# icyradio-lna.net
KiCad netlist of a schematic drawn in EAGLE
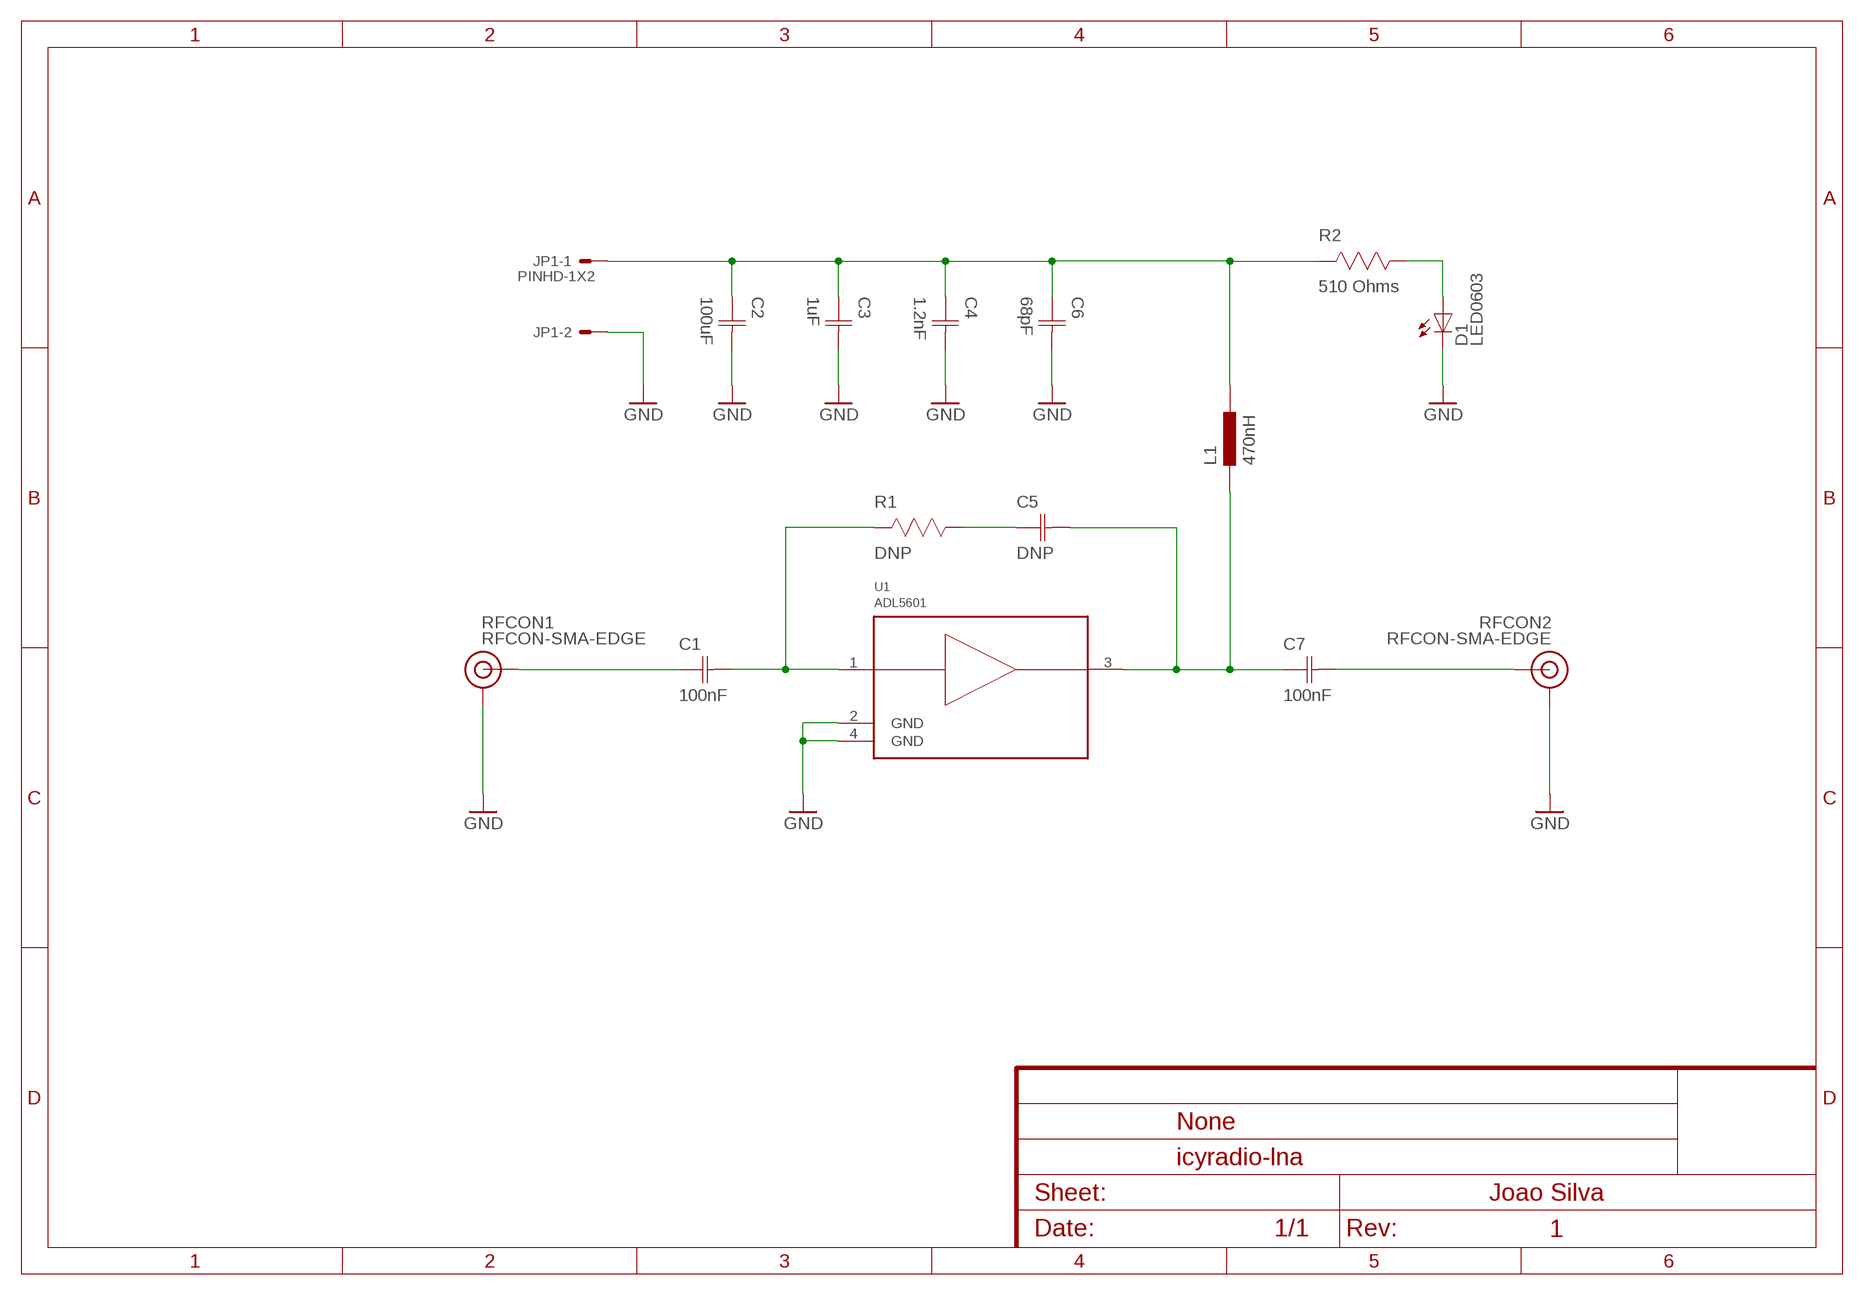
[diagram p0: schematic, sheet 1]

(export (version "E")
  (design (tool "Eeschema 10.0.6"))
  (components
    (comp (ref "C1")
      (value "100nF")
      (footprint "eagle-import:CAP0603")
      (libsource (lib "eagle-import") (part "CAPACITOR-0603"))
    )
    (comp (ref "C2")
      (value "100uF")
      (footprint "eagle-import:CAP1206")
      (libsource (lib "eagle-import") (part "CAPACITOR-1206"))
    )
    (comp (ref "C3")
      (value "1uF")
      (footprint "eagle-import:CAP0603")
      (libsource (lib "eagle-import") (part "CAPACITOR-0603"))
    )
    (comp (ref "C4")
      (value "1.2nF")
      (footprint "eagle-import:CAP0603")
      (libsource (lib "eagle-import") (part "CAPACITOR-0603"))
    )
    (comp (ref "C5")
      (value "DNP")
      (footprint "eagle-import:CAP0603")
      (libsource (lib "eagle-import") (part "CAPACITOR-0603"))
    )
    (comp (ref "C6")
      (value "68pF")
      (footprint "eagle-import:CAP0603")
      (libsource (lib "eagle-import") (part "CAPACITOR-0603"))
    )
    (comp (ref "C7")
      (value "100nF")
      (footprint "eagle-import:CAP0603")
      (libsource (lib "eagle-import") (part "CAPACITOR-0603"))
    )
    (comp (ref "D1")
      (value "LED0603")
      (footprint "eagle-import:0603")
      (libsource (lib "eagle-import") (part "LED0603"))
    )
    (comp (ref "JP1")
      (value "PINHD-1X2")
      (footprint "eagle-import:1X02")
      (libsource (lib "eagle-import") (part "PINHD-1X2"))
    )
    (comp (ref "L1")
      (value "470nH")
      (footprint "eagle-import:IND0603")
      (libsource (lib "eagle-import") (part "INDUCTOR-0603"))
    )
    (comp (ref "R1")
      (value "DNP")
      (footprint "eagle-import:RES0603")
      (libsource (lib "eagle-import") (part "RESISTOR-0603"))
    )
    (comp (ref "R2")
      (value "510 Ohms")
      (footprint "eagle-import:RES0603")
      (libsource (lib "eagle-import") (part "RESISTOR-0603"))
    )
    (comp (ref "RFCON1")
      (value "RFCON-SMA-EDGE")
      (footprint "eagle-import:SMA-EDGE")
      (libsource (lib "eagle-import") (part "RFCON-SMA-EDGE"))
    )
    (comp (ref "RFCON2")
      (value "RFCON-SMA-EDGE")
      (footprint "eagle-import:SMA-EDGE")
      (libsource (lib "eagle-import") (part "RFCON-SMA-EDGE"))
    )
    (comp (ref "U1")
      (value "ADL5601")
      (footprint "eagle-import:SOT89")
      (libsource (lib "eagle-import") (part "ADL5?601"))
    )
  )
  (nets
    (net (code "1") (name "GND") (class "Default")
      (node (ref "C2") (pin "2") (pinfunction "C2_2") (pintype "passive"))
      (node (ref "C3") (pin "2") (pinfunction "C2_2") (pintype "passive"))
      (node (ref "C4") (pin "2") (pinfunction "C2_2") (pintype "passive"))
      (node (ref "C6") (pin "2") (pinfunction "C2_2") (pintype "passive"))
      (node (ref "D1") (pin "C") (pinfunction "C_C") (pintype "passive"))
      (node (ref "JP1") (pin "2") (pinfunction "S_2") (pintype "passive"))
      (node (ref "RFCON1") (pin "GND@0") (pinfunction "GND_GND@0") (pintype "bidirectional"))
      (node (ref "RFCON1") (pin "GND@1") (pinfunction "GND_GND@1") (pintype "bidirectional"))
      (node (ref "RFCON1") (pin "GND@2") (pinfunction "GND_GND@2") (pintype "bidirectional"))
      (node (ref "RFCON1") (pin "GND@3") (pinfunction "GND_GND@3") (pintype "bidirectional"))
      (node (ref "RFCON2") (pin "GND@0") (pinfunction "GND_GND@0") (pintype "bidirectional"))
      (node (ref "RFCON2") (pin "GND@1") (pinfunction "GND_GND@1") (pintype "bidirectional"))
      (node (ref "RFCON2") (pin "GND@2") (pinfunction "GND_GND@2") (pintype "bidirectional"))
      (node (ref "RFCON2") (pin "GND@3") (pinfunction "GND_GND@3") (pintype "bidirectional"))
      (node (ref "U1") (pin "2") (pinfunction "GND_2") (pintype "bidirectional"))
      (node (ref "U1") (pin "4") (pinfunction "GND_4") (pintype "bidirectional"))
    )
    (net (code "2") (name "Net-(C1-C1)") (class "Default")
      (node (ref "C1") (pin "1") (pinfunction "C1_1") (pintype "passive"))
      (node (ref "RFCON1") (pin "SIG") (pinfunction "SIGNAL_SIG") (pintype "bidirectional"))
    )
    (net (code "3") (name "Net-(C1-C2)") (class "Default")
      (node (ref "C1") (pin "2") (pinfunction "C2_2") (pintype "passive"))
      (node (ref "R1") (pin "2") (pinfunction "2_2") (pintype "passive"))
      (node (ref "U1") (pin "1") (pinfunction "RFIN_1") (pintype "bidirectional"))
    )
    (net (code "4") (name "Net-(C2-C1)") (class "Default")
      (node (ref "C2") (pin "1") (pinfunction "C1_1") (pintype "passive"))
      (node (ref "C3") (pin "1") (pinfunction "C1_1") (pintype "passive"))
      (node (ref "C4") (pin "1") (pinfunction "C1_1") (pintype "passive"))
      (node (ref "C6") (pin "1") (pinfunction "C1_1") (pintype "passive"))
      (node (ref "JP1") (pin "1") (pinfunction "S_1") (pintype "passive"))
      (node (ref "L1") (pin "2") (pinfunction "2_2") (pintype "passive"))
      (node (ref "R2") (pin "2") (pinfunction "2_2") (pintype "passive"))
    )
    (net (code "5") (name "Net-(C5-C1)") (class "Default")
      (node (ref "C5") (pin "1") (pinfunction "C1_1") (pintype "passive"))
      (node (ref "R1") (pin "1") (pinfunction "1_1") (pintype "passive"))
    )
    (net (code "6") (name "Net-(C5-C2)") (class "Default")
      (node (ref "C5") (pin "2") (pinfunction "C2_2") (pintype "passive"))
      (node (ref "C7") (pin "1") (pinfunction "C1_1") (pintype "passive"))
      (node (ref "L1") (pin "1") (pinfunction "1_1") (pintype "passive"))
      (node (ref "U1") (pin "3") (pinfunction "RFOUT_3") (pintype "bidirectional"))
    )
    (net (code "7") (name "Net-(C7-C2)") (class "Default")
      (node (ref "C7") (pin "2") (pinfunction "C2_2") (pintype "passive"))
      (node (ref "RFCON2") (pin "SIG") (pinfunction "SIGNAL_SIG") (pintype "bidirectional"))
    )
    (net (code "8") (name "Net-(D1-PadA)") (class "Default")
      (node (ref "D1") (pin "A") (pinfunction "A_A") (pintype "passive"))
      (node (ref "R2") (pin "1") (pinfunction "1_1") (pintype "passive"))
    )
  )
)
